# Sheet2.net
KiCad netlist of a schematic drawn in Altium Designer
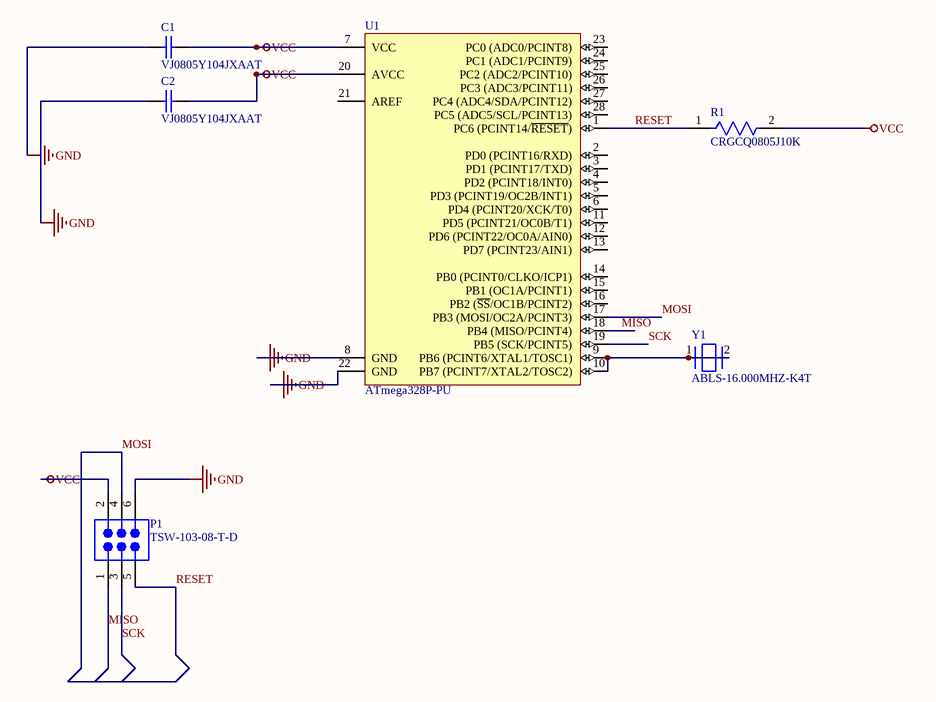
[diagram p0: Sheet2.SchDoc]

(export (version "E")
  (design (tool "Eeschema 10.0.6"))
  (components
    (comp (ref "C1")
      (value "VJ0805Y104JXAAT")
      (footprint "CAPC2013X145X48ML20T23")
      (fields (field (name "MANUFACTURER") "Vitramon"))
      (libsource (lib "Altium Content Vault") (part "CAP"))
    )
    (comp (ref "C2")
      (value "VJ0805Y104JXAAT")
      (footprint "CAPC2013X145X48ML20T23")
      (fields (field (name "MANUFACTURER") "Vitramon"))
      (libsource (lib "Altium Content Vault") (part "CAP"))
    )
    (comp (ref "P1")
      (value "TSW-103-08-T-D")
      (footprint "SMTC-TSW-103-08-X-D")
      (description "0.025\" SQ Post Header, Through-hole, Vertical, -55 to 105 degC, 2.54 mm Pitch, 6-Pin, Male, RoHS")
      (fields (field (name "MANUFACTURER") "Samtec"))
      (libsource (lib "Altium Content Vault") (part "SMTC-TSW-103-08-X-D"))
    )
    (comp (ref "R1")
      (value "CRGCQ0805J10K")
      (footprint "FP-CRGCQ0805-IPC_C")
      (description "CRGCQ0805 10KΩ 0.125W ±100ppm/°C 5% 150V")
      (fields (field (name "MANUFACTURER") "TE Connectivity"))
      (libsource (lib "Altium Content Vault") (part "1029c3af85768c4190bb7ad29bc67b5"))
    )
    (comp (ref "U1")
      (value "ATmega328P-PU")
      (footprint "28P3")
      (libsource (lib "Altium Content Vault") (part "MC-8B-ATM48-IL28"))
    )
    (comp (ref "Y1")
      (value "ABLS-16.000MHZ-K4T")
      (footprint "FP-ABLS-MFG")
      (description "16MHz ±30ppm Crystal 18pF 40 Ohms HC-49/US")
      (fields (field (name "TOLERANCE") "30ppm"))
      (libsource (lib "Altium Content Vault") (part "c23a69dc6c9e2f18f2079038eb95dd1"))
    )
  )
  (nets
    (net (code "1") (name "/MISO") (class "Default")
      (node (ref "P1") (pin "1") (pinfunction "1_1") (pintype "passive"))
      (node (ref "U1") (pin "18") (pinfunction "PB4_(MISO/PCINT4)_18") (pintype "bidirectional"))
    )
    (net (code "2") (name "/MOSI") (class "Default")
      (node (ref "P1") (pin "4") (pinfunction "4_4") (pintype "passive"))
      (node (ref "U1") (pin "17") (pinfunction "PB3_(MOSI/OC2A/PCINT3)_17") (pintype "bidirectional"))
    )
    (net (code "3") (name "/RESET") (class "Default")
      (node (ref "P1") (pin "5") (pinfunction "5_5") (pintype "passive"))
      (node (ref "R1") (pin "1") (pinfunction "1_1") (pintype "passive"))
      (node (ref "U1") (pin "1") (pinfunction "PC6_(PCINT14/~{RESET})_1") (pintype "bidirectional"))
    )
    (net (code "4") (name "/SCK") (class "Default")
      (node (ref "P1") (pin "3") (pinfunction "3_3") (pintype "passive"))
      (node (ref "U1") (pin "19") (pinfunction "PB5_(SCK/PCINT5)_19") (pintype "bidirectional"))
    )
    (net (code "5") (name "GND") (class "Default")
      (node (ref "C1") (pin "1") (pinfunction "1_1") (pintype "passive"))
      (node (ref "C2") (pin "1") (pinfunction "1_1") (pintype "passive"))
      (node (ref "P1") (pin "6") (pinfunction "6_6") (pintype "passive"))
      (node (ref "U1") (pin "22") (pinfunction "GND_22") (pintype "power_in"))
      (node (ref "U1") (pin "8") (pinfunction "GND_8") (pintype "power_in"))
    )
    (net (code "6") (name "Net-(U1-PB6_(PCINT6{slash}XTAL1{slash}TOSC1))") (class "Default")
      (node (ref "U1") (pin "10") (pinfunction "PB7_(PCINT7/XTAL2/TOSC2)_10") (pintype "bidirectional"))
      (node (ref "U1") (pin "9") (pinfunction "PB6_(PCINT6/XTAL1/TOSC1)_9") (pintype "bidirectional"))
      (node (ref "Y1") (pin "1") (pinfunction "1_1") (pintype "passive"))
      (node (ref "Y1") (pin "2") (pinfunction "2_2") (pintype "passive"))
    )
    (net (code "7") (name "VCC") (class "Default")
      (node (ref "C1") (pin "2") (pinfunction "2_2") (pintype "passive"))
      (node (ref "C2") (pin "2") (pinfunction "2_2") (pintype "passive"))
      (node (ref "P1") (pin "2") (pinfunction "2_2") (pintype "passive"))
      (node (ref "R1") (pin "2") (pinfunction "2_2") (pintype "passive"))
      (node (ref "U1") (pin "20") (pinfunction "AVCC_20") (pintype "power_in"))
      (node (ref "U1") (pin "7") (pinfunction "VCC_7") (pintype "power_in"))
    )
    (net (code "8") (name "unconnected-(U1-AREF-Pad21)") (class "Default")
      (node (ref "U1") (pin "21") (pinfunction "AREF_21") (pintype "power_in"))
    )
    (net (code "9") (name "unconnected-(U1-PB0_(PCINT0{slash}CLKO{slash}ICP1)-Pad14)") (class "Default")
      (node (ref "U1") (pin "14") (pinfunction "PB0_(PCINT0/CLKO/ICP1)_14") (pintype "bidirectional"))
    )
    (net (code "10") (name "unconnected-(U1-PB1_(OC1A{slash}PCINT1)-Pad15)") (class "Default")
      (node (ref "U1") (pin "15") (pinfunction "PB1_(OC1A/PCINT1)_15") (pintype "bidirectional"))
    )
    (net (code "11") (name "unconnected-(U1-PB2_(~{SS}{slash}OC1B{slash}PCINT2)-Pad16)") (class "Default")
      (node (ref "U1") (pin "16") (pinfunction "PB2_(~{SS}/OC1B/PCINT2)_16") (pintype "bidirectional"))
    )
    (net (code "12") (name "unconnected-(U1-PC0_(ADC0{slash}PCINT8)-Pad23)") (class "Default")
      (node (ref "U1") (pin "23") (pinfunction "PC0_(ADC0/PCINT8)_23") (pintype "bidirectional"))
    )
    (net (code "13") (name "unconnected-(U1-PC1_(ADC1{slash}PCINT9)-Pad24)") (class "Default")
      (node (ref "U1") (pin "24") (pinfunction "PC1_(ADC1/PCINT9)_24") (pintype "bidirectional"))
    )
    (net (code "14") (name "unconnected-(U1-PC2_(ADC2{slash}PCINT10)-Pad25)") (class "Default")
      (node (ref "U1") (pin "25") (pinfunction "PC2_(ADC2/PCINT10)_25") (pintype "bidirectional"))
    )
    (net (code "15") (name "unconnected-(U1-PC3_(ADC3{slash}PCINT11)-Pad26)") (class "Default")
      (node (ref "U1") (pin "26") (pinfunction "PC3_(ADC3/PCINT11)_26") (pintype "bidirectional"))
    )
    (net (code "16") (name "unconnected-(U1-PC4_(ADC4{slash}SDA{slash}PCINT12)-Pad27)") (class "Default")
      (node (ref "U1") (pin "27") (pinfunction "PC4_(ADC4/SDA/PCINT12)_27") (pintype "bidirectional"))
    )
    (net (code "17") (name "unconnected-(U1-PC5_(ADC5{slash}SCL{slash}PCINT13)-Pad28)") (class "Default")
      (node (ref "U1") (pin "28") (pinfunction "PC5_(ADC5/SCL/PCINT13)_28") (pintype "bidirectional"))
    )
    (net (code "18") (name "unconnected-(U1-PD0_(PCINT16{slash}RXD)-Pad2)") (class "Default")
      (node (ref "U1") (pin "2") (pinfunction "PD0_(PCINT16/RXD)_2") (pintype "bidirectional"))
    )
    (net (code "19") (name "unconnected-(U1-PD1_(PCINT17{slash}TXD)-Pad3)") (class "Default")
      (node (ref "U1") (pin "3") (pinfunction "PD1_(PCINT17/TXD)_3") (pintype "bidirectional"))
    )
    (net (code "20") (name "unconnected-(U1-PD2_(PCINT18{slash}INT0)-Pad4)") (class "Default")
      (node (ref "U1") (pin "4") (pinfunction "PD2_(PCINT18/INT0)_4") (pintype "bidirectional"))
    )
    (net (code "21") (name "unconnected-(U1-PD3_(PCINT19{slash}OC2B{slash}INT1)-Pad5)") (class "Default")
      (node (ref "U1") (pin "5") (pinfunction "PD3_(PCINT19/OC2B/INT1)_5") (pintype "bidirectional"))
    )
    (net (code "22") (name "unconnected-(U1-PD4_(PCINT20{slash}XCK{slash}T0)-Pad6)") (class "Default")
      (node (ref "U1") (pin "6") (pinfunction "PD4_(PCINT20/XCK/T0)_6") (pintype "bidirectional"))
    )
    (net (code "23") (name "unconnected-(U1-PD5_(PCINT21{slash}OC0B{slash}T1)-Pad11)") (class "Default")
      (node (ref "U1") (pin "11") (pinfunction "PD5_(PCINT21/OC0B/T1)_11") (pintype "bidirectional"))
    )
    (net (code "24") (name "unconnected-(U1-PD6_(PCINT22{slash}OC0A{slash}AIN0)-Pad12)") (class "Default")
      (node (ref "U1") (pin "12") (pinfunction "PD6_(PCINT22/OC0A/AIN0)_12") (pintype "bidirectional"))
    )
    (net (code "25") (name "unconnected-(U1-PD7_(PCINT23{slash}AIN1)-Pad13)") (class "Default")
      (node (ref "U1") (pin "13") (pinfunction "PD7_(PCINT23/AIN1)_13") (pintype "bidirectional"))
    )
  )
)
